# PSPS_AVNC_SRD_CS_combined-2021-02-07.net
KiCad netlist of a schematic drawn in EAGLE
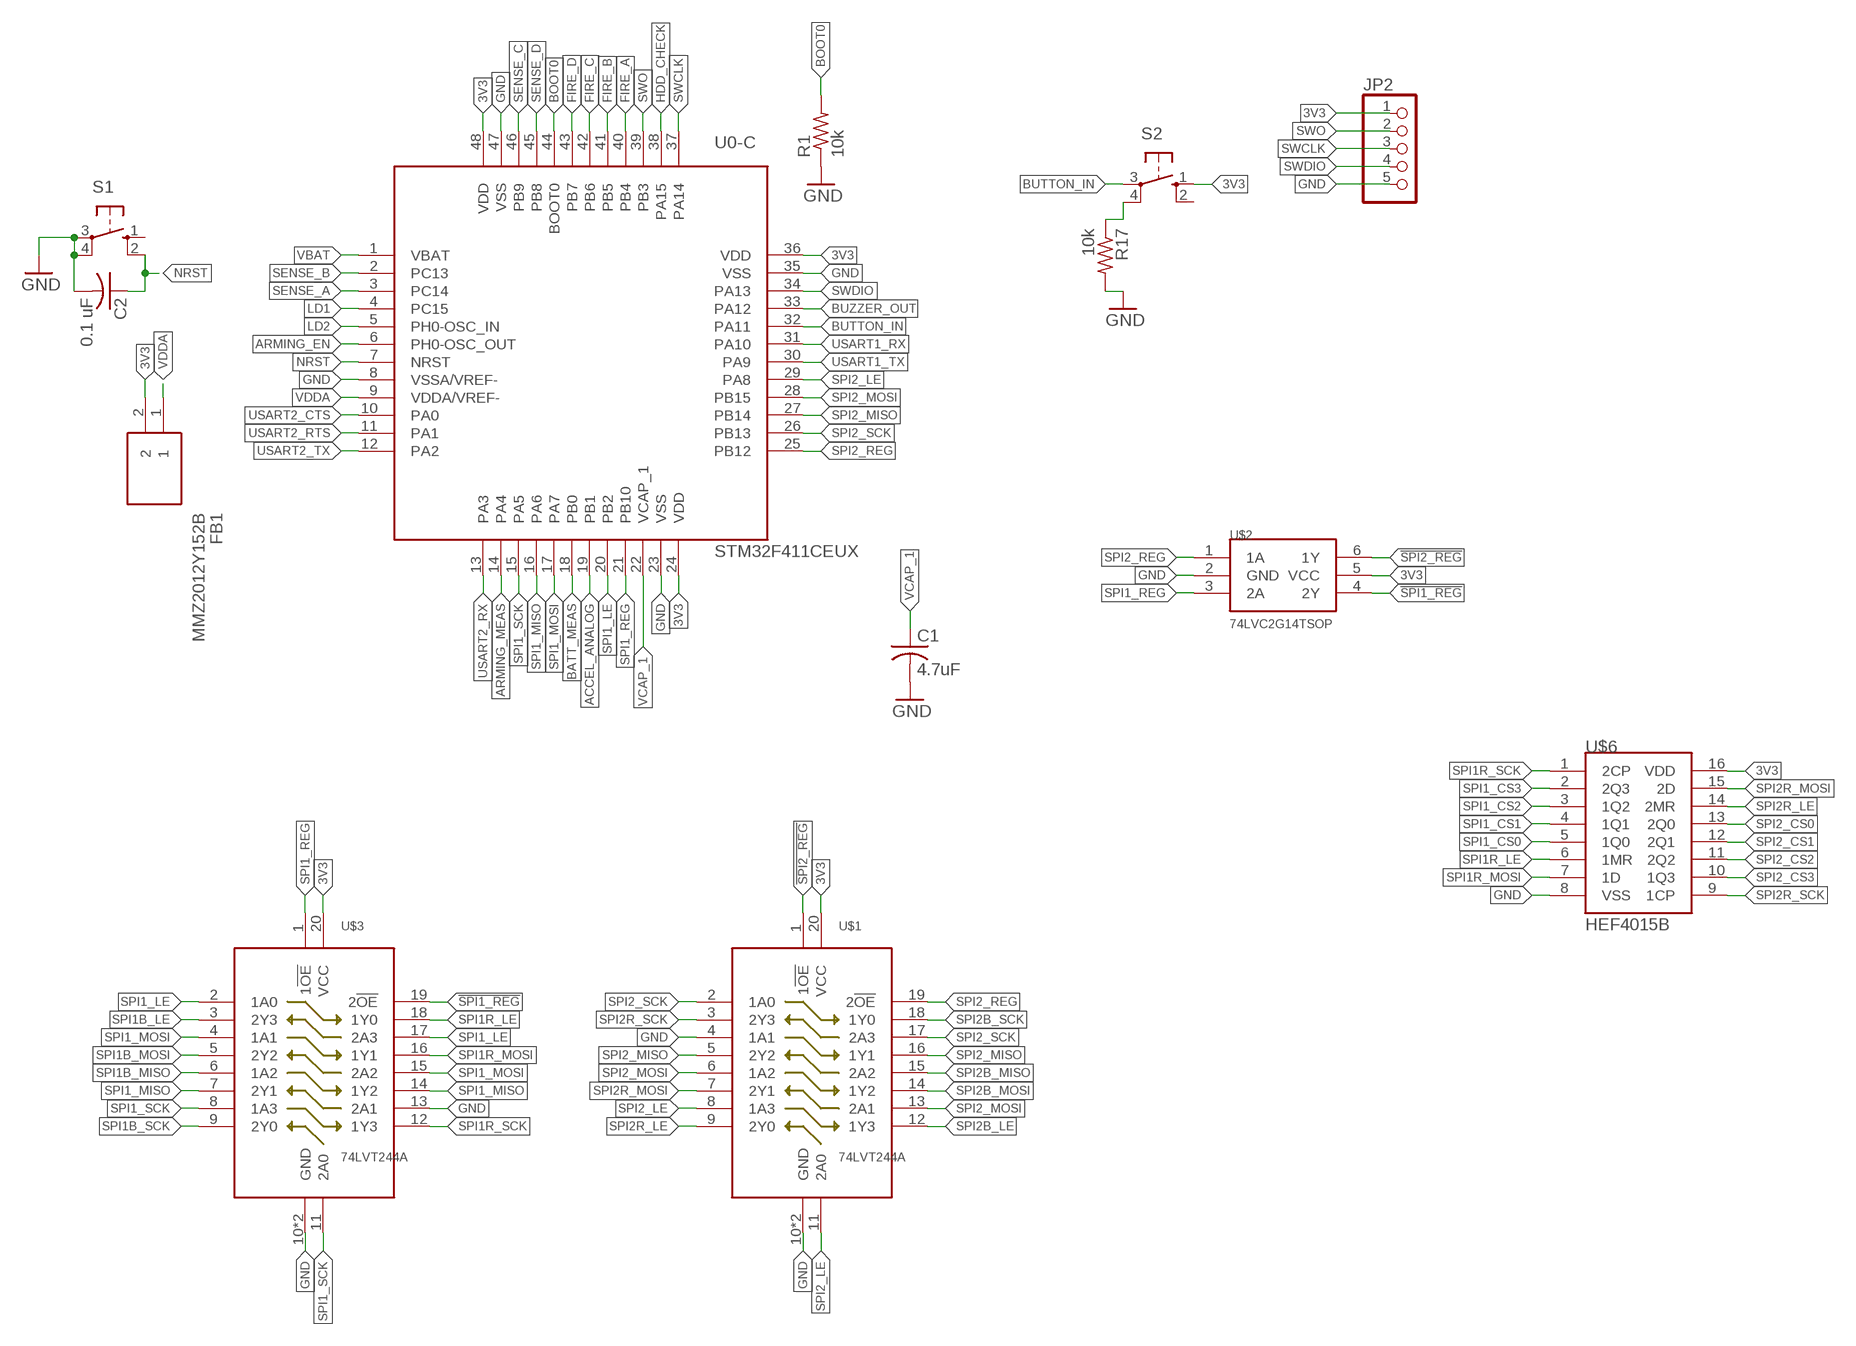
[diagram p0: schematic, sheet 1, part 1 of 2]
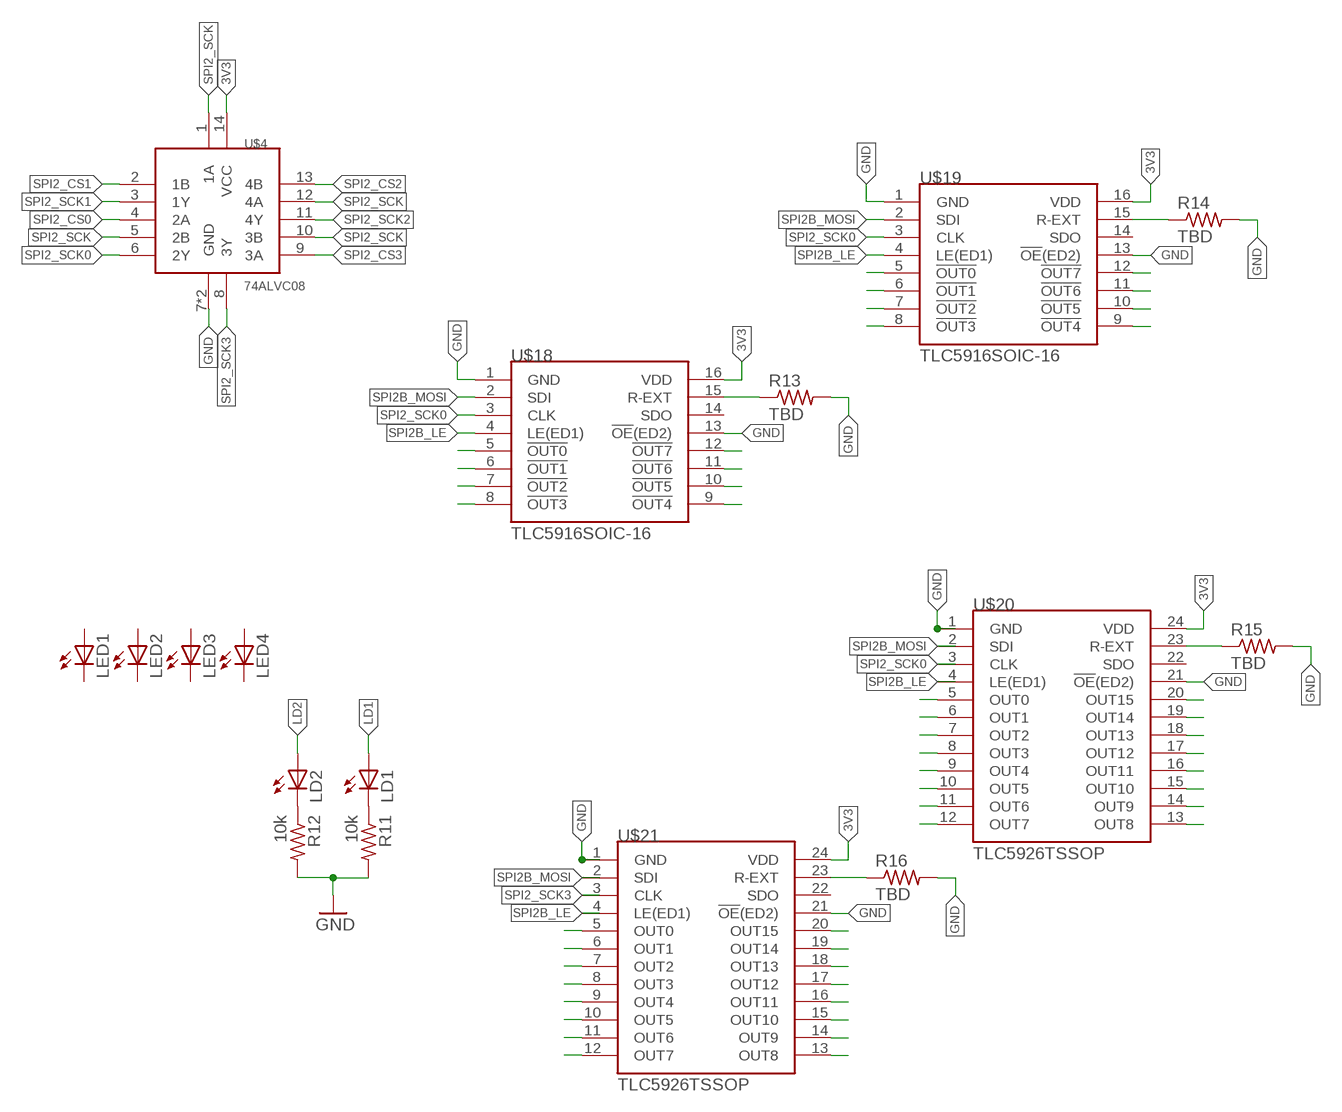
[diagram p1: schematic, sheet 1, part 2 of 2]
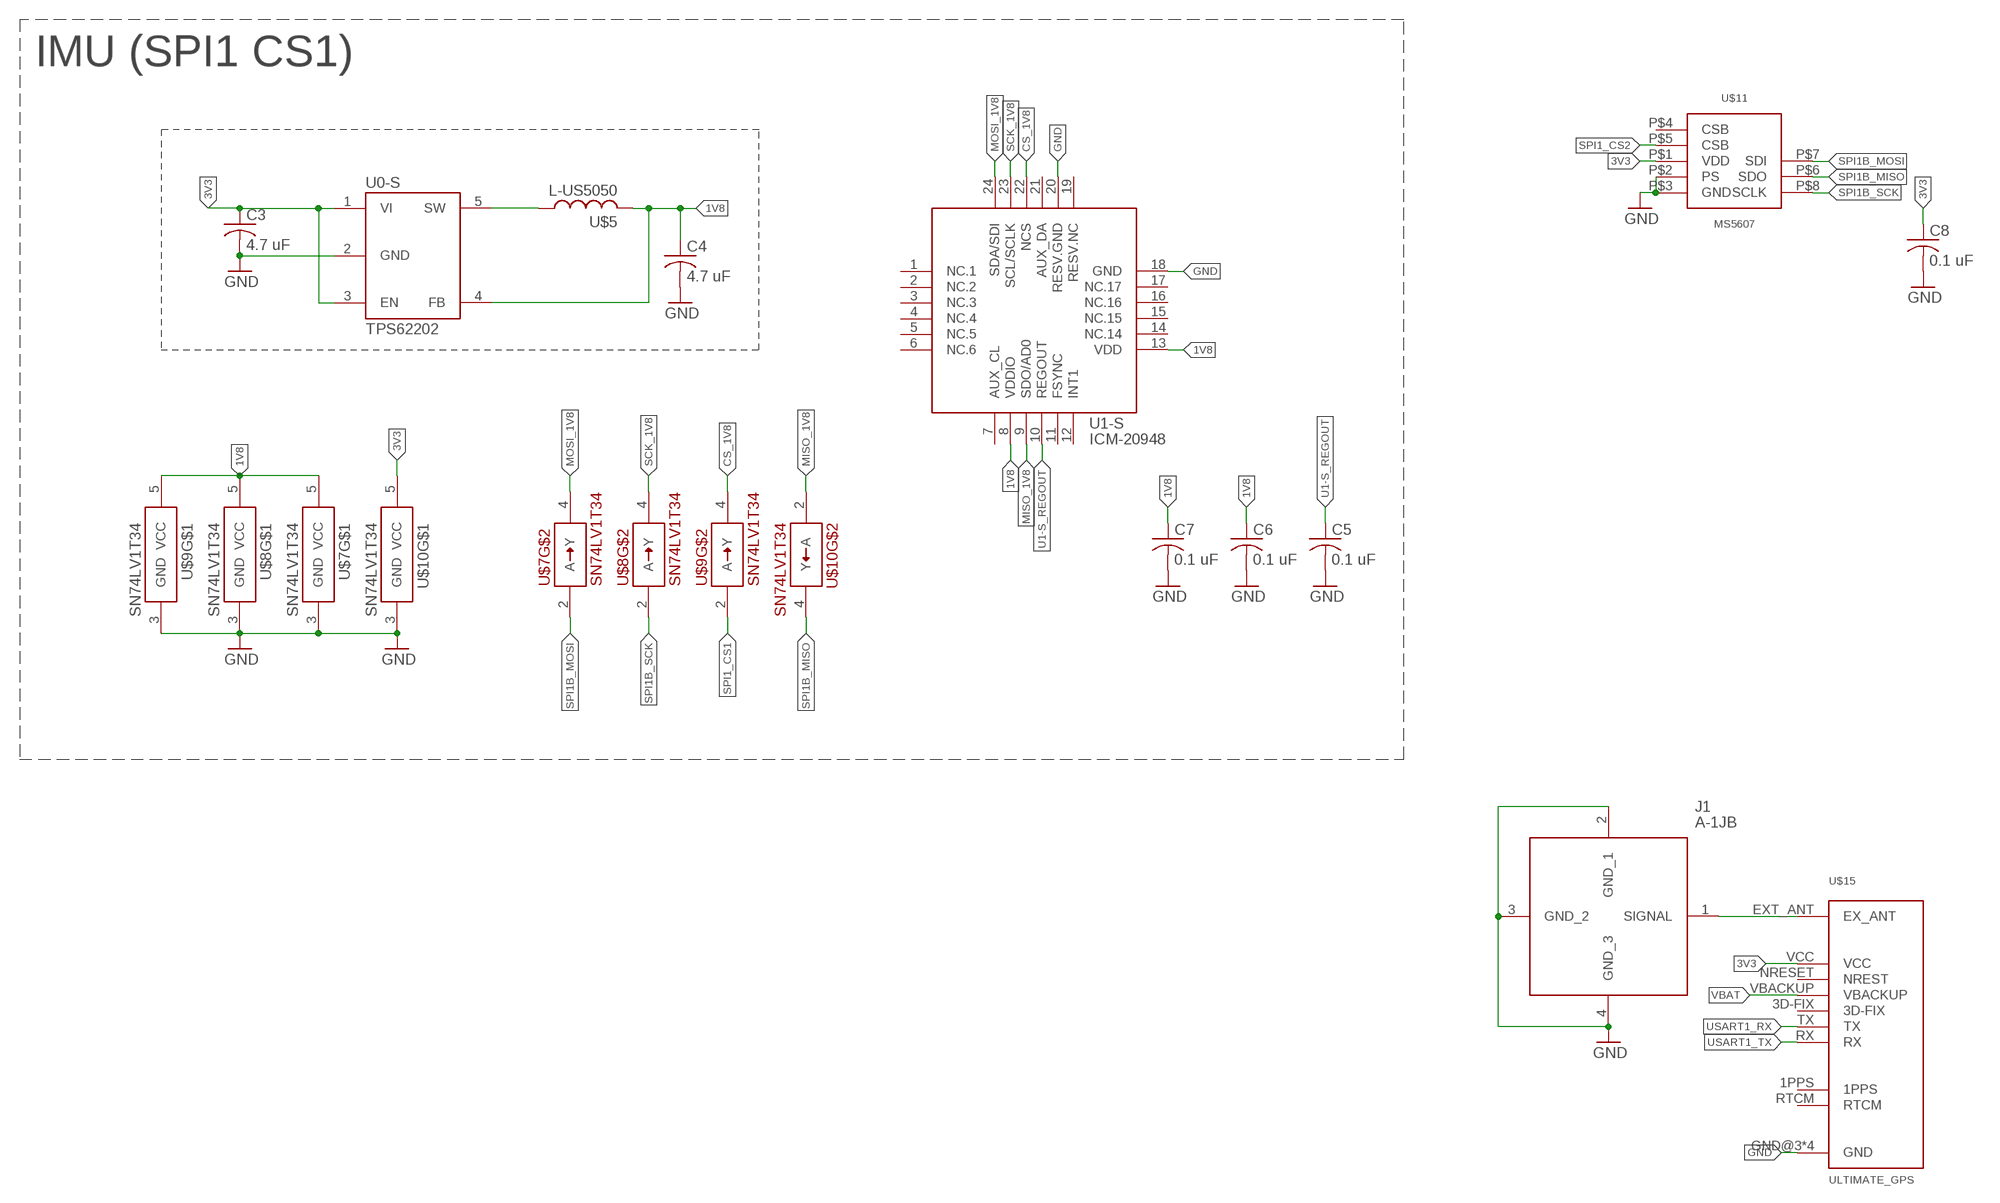
[diagram p2: schematic, sheet 2, part 1 of 2]
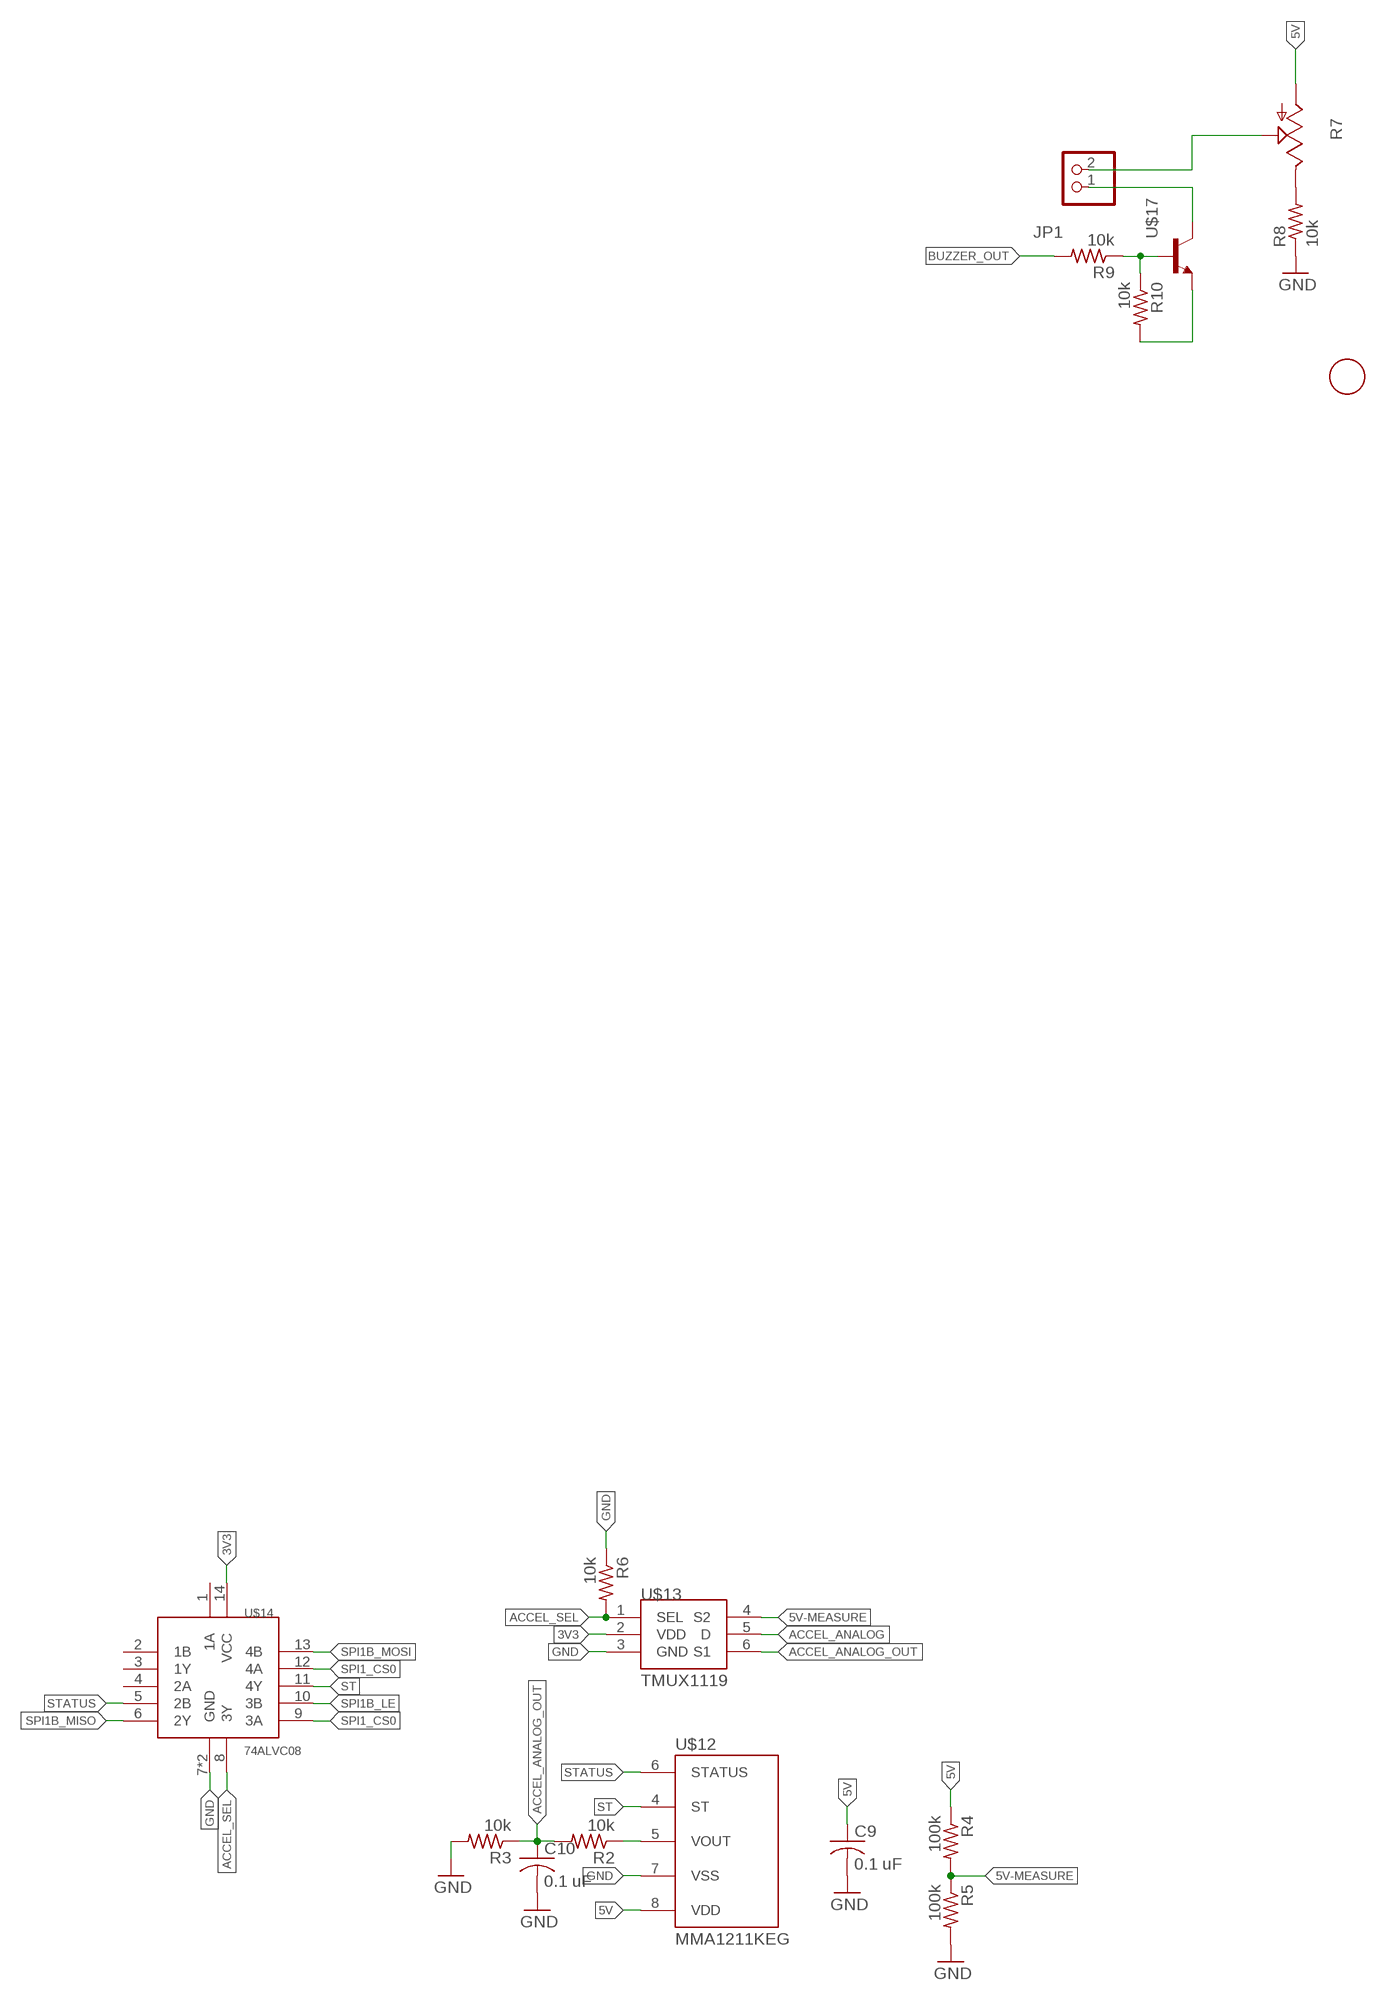
[diagram p3: schematic, sheet 2, part 2 of 2]

(export (version "E")
  (design (tool "Eeschema 10.0.6"))
  (components
    (comp (ref "C1")
      (value "4.7uF")
      (footprint "eagle-import:C0805")
      (libsource (lib "eagle-import") (part "C-USC0805"))
    )
    (comp (ref "C2")
      (value "0.1 uF")
      (footprint "eagle-import:C0805")
      (libsource (lib "eagle-import") (part "C-USC0805"))
    )
    (comp (ref "FB1")
      (value "MMZ2012Y152B")
      (footprint "eagle-import:BEADC2012X105N")
      (fields (field (name "MOUSER_PART_NUMBER") "810-MMZ2012Y152B"))
      (libsource (lib "eagle-import") (part "MMZ2012Y152B"))
    )
    (comp (ref "JP2")
      (value "PINHD-1X5")
      (footprint "eagle-import:1X05")
      (libsource (lib "eagle-import") (part "PINHD-1X5"))
    )
    (comp (ref "LD1")
      (value "LEDCHIP-LED0805")
      (footprint "eagle-import:CHIP-LED0805")
      (libsource (lib "eagle-import") (part "LEDCHIP-LED0805"))
    )
    (comp (ref "LD2")
      (value "LEDCHIP-LED0805")
      (footprint "eagle-import:CHIP-LED0805")
      (libsource (lib "eagle-import") (part "LEDCHIP-LED0805"))
    )
    (comp (ref "LED1")
      (value "LEDCHIP-LED0805")
      (footprint "eagle-import:CHIP-LED0805")
      (libsource (lib "eagle-import") (part "LEDCHIP-LED0805"))
    )
    (comp (ref "LED2")
      (value "LEDCHIP-LED0805")
      (footprint "eagle-import:CHIP-LED0805")
      (libsource (lib "eagle-import") (part "LEDCHIP-LED0805"))
    )
    (comp (ref "LED3")
      (value "LEDCHIP-LED0805")
      (footprint "eagle-import:CHIP-LED0805")
      (libsource (lib "eagle-import") (part "LEDCHIP-LED0805"))
    )
    (comp (ref "LED4")
      (value "LEDCHIP-LED0805")
      (footprint "eagle-import:CHIP-LED0805")
      (libsource (lib "eagle-import") (part "LEDCHIP-LED0805"))
    )
    (comp (ref "R1")
      (value "10k")
      (footprint "eagle-import:M0805")
      (libsource (lib "eagle-import") (part "R-US_M0805"))
    )
    (comp (ref "R11")
      (value "10k")
      (footprint "eagle-import:M0805")
      (libsource (lib "eagle-import") (part "R-US_M0805"))
    )
    (comp (ref "R12")
      (value "10k")
      (footprint "eagle-import:M0805")
      (libsource (lib "eagle-import") (part "R-US_M0805"))
    )
    (comp (ref "R13")
      (value "TBD")
      (footprint "eagle-import:M0805")
      (libsource (lib "eagle-import") (part "R-US_M0805"))
    )
    (comp (ref "R14")
      (value "TBD")
      (footprint "eagle-import:M0805")
      (libsource (lib "eagle-import") (part "R-US_M0805"))
    )
    (comp (ref "R15")
      (value "TBD")
      (footprint "eagle-import:M0805")
      (libsource (lib "eagle-import") (part "R-US_M0805"))
    )
    (comp (ref "R16")
      (value "TBD")
      (footprint "eagle-import:M0805")
      (libsource (lib "eagle-import") (part "R-US_M0805"))
    )
    (comp (ref "R17")
      (value "10k")
      (footprint "eagle-import:M0805")
      (libsource (lib "eagle-import") (part "R-US_M0805"))
    )
    (comp (ref "S1")
      (value "10-XX")
      (footprint "eagle-import:B3F-10XX")
      (fields (field (name "MPN") "B3F-1000"))
      (libsource (lib "eagle-import") (part "10-XX"))
    )
    (comp (ref "S2")
      (value "10-XX")
      (footprint "eagle-import:B3F-10XX")
      (fields (field (name "MPN") "B3F-1000"))
      (libsource (lib "eagle-import") (part "10-XX"))
    )
    (comp (ref "U$1")
      (value "74LVT244A")
      (footprint "eagle-import:QFN50P450X250X100-21T300X100N")
      (libsource (lib "eagle-import") (part "74LVT244A"))
    )
    (comp (ref "U$2")
      (value "74LVC2G14TSOP")
      (footprint "eagle-import:SOP95P280X110-6N")
      (libsource (lib "eagle-import") (part "74LVC2G14TSOP"))
    )
    (comp (ref "U$3")
      (value "74LVT244A")
      (footprint "eagle-import:QFN50P450X250X100-21T300X100N")
      (libsource (lib "eagle-import") (part "74LVT244A"))
    )
    (comp (ref "U$4")
      (value "74ALVC08")
      (footprint "eagle-import:QFN50P300X250X100-15T150X100N")
      (libsource (lib "eagle-import") (part "74ALVC08"))
    )
    (comp (ref "U$6")
      (value "HEF4015B")
      (footprint "eagle-import:SOIC127P600X265-16N")
      (libsource (lib "eagle-import") (part "HEF4015B"))
    )
    (comp (ref "U$18")
      (value "TLC5916SOIC-16")
      (footprint "eagle-import:SOIC127P600X175-16N")
      (libsource (lib "eagle-import") (part "TLC5916SOIC-16"))
    )
    (comp (ref "U$19")
      (value "TLC5916SOIC-16")
      (footprint "eagle-import:SOIC127P600X175-16N")
      (libsource (lib "eagle-import") (part "TLC5916SOIC-16"))
    )
    (comp (ref "U$20")
      (value "TLC5926TSSOP")
      (footprint "eagle-import:SOP65P640X120-24N")
      (libsource (lib "eagle-import") (part "TLC5926TSSOP"))
    )
    (comp (ref "U$21")
      (value "TLC5926TSSOP")
      (footprint "eagle-import:SOP65P640X120-24N")
      (libsource (lib "eagle-import") (part "TLC5926TSSOP"))
    )
    (comp (ref "U0-C")
      (value "STM32F411CEUX")
      (footprint "eagle-import:QFN50P700X700X50-49T560N")
      (libsource (lib "eagle-import") (part "STM32F411CEUX"))
    )
    (comp (ref "C3")
      (value "4.7 uF")
      (footprint "eagle-import:C0805")
      (libsource (lib "eagle-import") (part "C-USC0805"))
    )
    (comp (ref "C4")
      (value "4.7 uF")
      (footprint "eagle-import:C0805")
      (libsource (lib "eagle-import") (part "C-USC0805"))
    )
    (comp (ref "C5")
      (value "0.1 uF")
      (footprint "eagle-import:C0805")
      (libsource (lib "eagle-import") (part "C-USC0805"))
    )
    (comp (ref "C6")
      (value "0.1 uF")
      (footprint "eagle-import:C0805")
      (libsource (lib "eagle-import") (part "C-USC0805"))
    )
    (comp (ref "C7")
      (value "0.1 uF")
      (footprint "eagle-import:C0805")
      (libsource (lib "eagle-import") (part "C-USC0805"))
    )
    (comp (ref "C8")
      (value "0.1 uF")
      (footprint "eagle-import:C0805")
      (libsource (lib "eagle-import") (part "C-USC0805"))
    )
    (comp (ref "C9")
      (value "0.1 uF")
      (footprint "eagle-import:C0805")
      (libsource (lib "eagle-import") (part "C-USC0805"))
    )
    (comp (ref "C10")
      (value "0.1 uF")
      (footprint "eagle-import:C0805")
      (libsource (lib "eagle-import") (part "C-USC0805"))
    )
    (comp (ref "J1")
      (value "A-1JB")
      (footprint "eagle-import:A1JB")
      (fields (field (name "MOUSER_PART_NUMBER") "523-A-1JB"))
      (libsource (lib "eagle-import") (part "A-1JB"))
    )
    (comp (ref "JP1")
      (value "PINHD-1X2")
      (footprint "eagle-import:1X02")
      (libsource (lib "eagle-import") (part "PINHD-1X2"))
    )
    (comp (ref "R2")
      (value "10k")
      (footprint "eagle-import:M0805")
      (libsource (lib "eagle-import") (part "R-US_M0805"))
    )
    (comp (ref "R3")
      (value "10k")
      (footprint "eagle-import:M0805")
      (libsource (lib "eagle-import") (part "R-US_M0805"))
    )
    (comp (ref "R4")
      (value "100k")
      (footprint "eagle-import:M0805")
      (libsource (lib "eagle-import") (part "R-US_M0805"))
    )
    (comp (ref "R5")
      (value "100k")
      (footprint "eagle-import:M0805")
      (libsource (lib "eagle-import") (part "R-US_M0805"))
    )
    (comp (ref "R6")
      (value "10k")
      (footprint "eagle-import:M0805")
      (libsource (lib "eagle-import") (part "R-US_M0805"))
    )
    (comp (ref "R7")
      (value "TRIM_US-LI10")
      (footprint "eagle-import:LI10")
      (libsource (lib "eagle-import") (part "TRIM_US-LI10"))
    )
    (comp (ref "R8")
      (value "10k")
      (footprint "eagle-import:M0805")
      (libsource (lib "eagle-import") (part "R-US_M0805"))
    )
    (comp (ref "R9")
      (value "10k")
      (footprint "eagle-import:M0805")
      (libsource (lib "eagle-import") (part "R-US_M0805"))
    )
    (comp (ref "R10")
      (value "10k")
      (footprint "eagle-import:M0805")
      (libsource (lib "eagle-import") (part "R-US_M0805"))
    )
    (comp (ref "U$5")
      (value "L-US5050")
      (footprint "eagle-import:INDDFN1250X1250X600-2N")
      (libsource (lib "eagle-import") (part "L-US5050"))
    )
    (comp (ref "U$7")
      (value "SN74LV1T34")
      (footprint "eagle-import:SOT65P210X110-5")
      (libsource (lib "eagle-import") (part "SN74LV1T34"))
    )
    (comp (ref "U$8")
      (value "SN74LV1T34")
      (footprint "eagle-import:SOT65P210X110-5")
      (libsource (lib "eagle-import") (part "SN74LV1T34"))
    )
    (comp (ref "U$9")
      (value "SN74LV1T34")
      (footprint "eagle-import:SOT65P210X110-5")
      (libsource (lib "eagle-import") (part "SN74LV1T34"))
    )
    (comp (ref "U$10")
      (value "SN74LV1T34")
      (footprint "eagle-import:SOT65P210X110-5")
      (libsource (lib "eagle-import") (part "SN74LV1T34"))
    )
    (comp (ref "U$11")
      (value "MS5607")
      (footprint "eagle-import:MS5607")
      (libsource (lib "eagle-import") (part "MS5607"))
    )
    (comp (ref "U$12")
      (value "MMA1211KEG")
      (footprint "eagle-import:SOIC127P1041X355-16N")
      (libsource (lib "eagle-import") (part "MMA1211KEG"))
    )
    (comp (ref "U$13")
      (value "TMUX1119")
      (footprint "eagle-import:SOP95P280X145-6N")
      (libsource (lib "eagle-import") (part "TMUX1119"))
    )
    (comp (ref "U$14")
      (value "74ALVC08")
      (footprint "eagle-import:QFN50P300X250X100-15T150X100N")
      (libsource (lib "eagle-import") (part "74ALVC08"))
    )
    (comp (ref "U$15")
      (value "ULTIMATE_GPS")
      (footprint "eagle-import:FGPMMOPA6H")
      (libsource (lib "eagle-import") (part "ULTIMATE_GPS"))
    )
    (comp (ref "U$16")
      (value "UXCELL_BUZZER")
      (footprint "eagle-import:UXCELL_BUZZER")
      (libsource (lib "eagle-import") (part "UXCELL_BUZZER"))
    )
    (comp (ref "U$17")
      (value "NPN_TRANSISTOR")
      (footprint "eagle-import:SOT23")
      (libsource (lib "eagle-import") (part "NPN_TRANSISTOR"))
    )
    (comp (ref "U0-S")
      (value "TPS62202")
      (footprint "eagle-import:SOT95P280X145-5")
      (libsource (lib "eagle-import") (part "TPS62202"))
    )
    (comp (ref "U1-S")
      (value "ICM-20948")
      (footprint "eagle-import:QFN40P300X300X105-25T159X175")
      (libsource (lib "eagle-import") (part "ICM-20948"))
    )
  )
  (nets
    (net (code "1") (name "1V8") (class "Default")
      (node (ref "C4") (pin "1") (pinfunction "1_1") (pintype "passive"))
      (node (ref "C6") (pin "1") (pinfunction "1_1") (pintype "passive"))
      (node (ref "C7") (pin "1") (pinfunction "1_1") (pintype "passive"))
      (node (ref "U$5") (pin "2") (pinfunction "2_2") (pintype "passive"))
      (node (ref "U$7") (pin "5") (pinfunction "VCC_5") (pintype "bidirectional"))
      (node (ref "U$8") (pin "5") (pinfunction "VCC_5") (pintype "bidirectional"))
      (node (ref "U$9") (pin "5") (pinfunction "VCC_5") (pintype "bidirectional"))
      (node (ref "U0-S") (pin "4") (pinfunction "FB_4") (pintype "bidirectional"))
      (node (ref "U1-S") (pin "13") (pinfunction "VDD_13") (pintype "bidirectional"))
      (node (ref "U1-S") (pin "8") (pinfunction "VDDIO_8") (pintype "bidirectional"))
    )
    (net (code "2") (name "3V3") (class "Default")
      (node (ref "C3") (pin "1") (pinfunction "1_1") (pintype "passive"))
      (node (ref "C8") (pin "1") (pinfunction "1_1") (pintype "passive"))
      (node (ref "FB1") (pin "2") (pinfunction "2_2") (pintype "bidirectional"))
      (node (ref "JP2") (pin "1") (pinfunction "1_1") (pintype "passive"))
      (node (ref "S2") (pin "1") (pinfunction "S_1") (pintype "passive"))
      (node (ref "U$1") (pin "20") (pinfunction "VCC_20") (pintype "bidirectional"))
      (node (ref "U$10") (pin "5") (pinfunction "VCC_5") (pintype "bidirectional"))
      (node (ref "U$11") (pin "P$1") (pinfunction "VDD_P$1") (pintype "bidirectional"))
      (node (ref "U$13") (pin "2") (pinfunction "VDD_2") (pintype "bidirectional"))
      (node (ref "U$14") (pin "14") (pinfunction "VCC_14") (pintype "bidirectional"))
      (node (ref "U$15") (pin "VCC") (pinfunction "VCC_VCC") (pintype "bidirectional"))
      (node (ref "U$18") (pin "16") (pinfunction "VDD_16") (pintype "bidirectional"))
      (node (ref "U$19") (pin "16") (pinfunction "VDD_16") (pintype "bidirectional"))
      (node (ref "U$2") (pin "5") (pinfunction "VCC_5") (pintype "bidirectional"))
      (node (ref "U$20") (pin "24") (pinfunction "VDD_24") (pintype "bidirectional"))
      (node (ref "U$21") (pin "24") (pinfunction "VDD_24") (pintype "bidirectional"))
      (node (ref "U$3") (pin "20") (pinfunction "VCC_20") (pintype "bidirectional"))
      (node (ref "U$4") (pin "14") (pinfunction "VCC_14") (pintype "bidirectional"))
      (node (ref "U$6") (pin "16") (pinfunction "VDD_16") (pintype "bidirectional"))
      (node (ref "U0-C") (pin "24") (pinfunction "VDD_24") (pintype "bidirectional"))
      (node (ref "U0-C") (pin "36") (pinfunction "VDD_36") (pintype "bidirectional"))
      (node (ref "U0-C") (pin "48") (pinfunction "VDD_48") (pintype "bidirectional"))
      (node (ref "U0-S") (pin "1") (pinfunction "VI_1") (pintype "bidirectional"))
      (node (ref "U0-S") (pin "3") (pinfunction "EN_3") (pintype "bidirectional"))
    )
    (net (code "3") (name "5V") (class "Default")
      (node (ref "C9") (pin "1") (pinfunction "1_1") (pintype "passive"))
      (node (ref "R4") (pin "1") (pinfunction "1_1") (pintype "passive"))
      (node (ref "R7") (pin "A") (pinfunction "A_A") (pintype "passive"))
      (node (ref "U$12") (pin "8") (pinfunction "VDD_8") (pintype "bidirectional"))
    )
    (net (code "4") (name "5V-MEASURE") (class "Default")
      (node (ref "R4") (pin "2") (pinfunction "2_2") (pintype "passive"))
      (node (ref "R5") (pin "1") (pinfunction "1_1") (pintype "passive"))
      (node (ref "U$13") (pin "4") (pinfunction "S2_4") (pintype "bidirectional"))
    )
    (net (code "5") (name "ACCEL_ANALOG") (class "Default")
      (node (ref "U$13") (pin "5") (pinfunction "D_5") (pintype "bidirectional"))
      (node (ref "U0-C") (pin "19") (pinfunction "PB1_19") (pintype "bidirectional"))
    )
    (net (code "6") (name "ACCEL_ANALOG_OUT") (class "Default")
      (node (ref "C10") (pin "1") (pinfunction "1_1") (pintype "passive"))
      (node (ref "R2") (pin "2") (pinfunction "2_2") (pintype "passive"))
      (node (ref "R3") (pin "1") (pinfunction "1_1") (pintype "passive"))
      (node (ref "U$13") (pin "6") (pinfunction "S1_6") (pintype "bidirectional"))
    )
    (net (code "7") (name "ACCEL_SEL") (class "Default")
      (node (ref "R6") (pin "2") (pinfunction "2_2") (pintype "passive"))
      (node (ref "U$13") (pin "1") (pinfunction "SEL_1") (pintype "bidirectional"))
      (node (ref "U$14") (pin "8") (pinfunction "3Y_8") (pintype "bidirectional"))
    )
    (net (code "8") (name "ARMING_EN") (class "Default")
      (node (ref "U0-C") (pin "6") (pinfunction "PH0-OSC_OUT_6") (pintype "bidirectional"))
    )
    (net (code "9") (name "ARMING_MEAS") (class "Default")
      (node (ref "U0-C") (pin "14") (pinfunction "PA4_14") (pintype "bidirectional"))
    )
    (net (code "10") (name "BATT_MEAS") (class "Default")
      (node (ref "U0-C") (pin "18") (pinfunction "PB0_18") (pintype "bidirectional"))
    )
    (net (code "11") (name "BOOT0") (class "Default")
      (node (ref "R1") (pin "2") (pinfunction "2_2") (pintype "passive"))
      (node (ref "U0-C") (pin "44") (pinfunction "BOOT0_44") (pintype "bidirectional"))
    )
    (net (code "12") (name "BUTTON_IN") (class "Default")
      (node (ref "S2") (pin "3") (pinfunction "P_3") (pintype "passive"))
      (node (ref "U0-C") (pin "32") (pinfunction "PA11_32") (pintype "bidirectional"))
    )
    (net (code "13") (name "BUZZER_OUT") (class "Default")
      (node (ref "R9") (pin "2") (pinfunction "2_2") (pintype "passive"))
      (node (ref "U0-C") (pin "33") (pinfunction "PA12_33") (pintype "bidirectional"))
    )
    (net (code "14") (name "CS_1V8") (class "Default")
      (node (ref "U$9") (pin "4") (pinfunction "Y_4") (pintype "bidirectional"))
      (node (ref "U1-S") (pin "22") (pinfunction "NCS_22") (pintype "bidirectional"))
    )
    (net (code "15") (name "FIRE_A") (class "Default")
      (node (ref "U0-C") (pin "40") (pinfunction "PB4_40") (pintype "bidirectional"))
    )
    (net (code "16") (name "FIRE_B") (class "Default")
      (node (ref "U0-C") (pin "41") (pinfunction "PB5_41") (pintype "bidirectional"))
    )
    (net (code "17") (name "FIRE_C") (class "Default")
      (node (ref "U0-C") (pin "42") (pinfunction "PB6_42") (pintype "bidirectional"))
    )
    (net (code "18") (name "FIRE_D") (class "Default")
      (node (ref "U0-C") (pin "43") (pinfunction "PB7_43") (pintype "bidirectional"))
    )
    (net (code "19") (name "GND") (class "Default")
      (node (ref "C1") (pin "2") (pinfunction "2_2") (pintype "passive"))
      (node (ref "C10") (pin "2") (pinfunction "2_2") (pintype "passive"))
      (node (ref "C2") (pin "2") (pinfunction "2_2") (pintype "passive"))
      (node (ref "C3") (pin "2") (pinfunction "2_2") (pintype "passive"))
      (node (ref "C4") (pin "2") (pinfunction "2_2") (pintype "passive"))
      (node (ref "C5") (pin "2") (pinfunction "2_2") (pintype "passive"))
      (node (ref "C6") (pin "2") (pinfunction "2_2") (pintype "passive"))
      (node (ref "C7") (pin "2") (pinfunction "2_2") (pintype "passive"))
      (node (ref "C8") (pin "2") (pinfunction "2_2") (pintype "passive"))
      (node (ref "C9") (pin "2") (pinfunction "2_2") (pintype "passive"))
      (node (ref "J1") (pin "2") (pinfunction "GND_1_2") (pintype "bidirectional"))
      (node (ref "J1") (pin "3") (pinfunction "GND_2_3") (pintype "bidirectional"))
      (node (ref "J1") (pin "4") (pinfunction "GND_3_4") (pintype "bidirectional"))
      (node (ref "JP2") (pin "5") (pinfunction "5_5") (pintype "passive"))
      (node (ref "R1") (pin "1") (pinfunction "1_1") (pintype "passive"))
      (node (ref "R11") (pin "2") (pinfunction "2_2") (pintype "passive"))
      (node (ref "R12") (pin "2") (pinfunction "2_2") (pintype "passive"))
      (node (ref "R13") (pin "2") (pinfunction "2_2") (pintype "passive"))
      (node (ref "R14") (pin "2") (pinfunction "2_2") (pintype "passive"))
      (node (ref "R15") (pin "2") (pinfunction "2_2") (pintype "passive"))
      (node (ref "R16") (pin "2") (pinfunction "2_2") (pintype "passive"))
      (node (ref "R17") (pin "2") (pinfunction "2_2") (pintype "passive"))
      (node (ref "R3") (pin "2") (pinfunction "2_2") (pintype "passive"))
      (node (ref "R5") (pin "2") (pinfunction "2_2") (pintype "passive"))
      (node (ref "R6") (pin "1") (pinfunction "1_1") (pintype "passive"))
      (node (ref "R8") (pin "1") (pinfunction "1_1") (pintype "passive"))
      (node (ref "S1") (pin "3") (pinfunction "P_3") (pintype "passive"))
      (node (ref "S1") (pin "4") (pinfunction "P1_4") (pintype "passive"))
      (node (ref "U$1") (pin "10") (pinfunction "GND_10") (pintype "bidirectional"))
      (node (ref "U$1") (pin "21") (pinfunction "GND_21") (pintype "bidirectional"))
      (node (ref "U$1") (pin "4") (pinfunction "1A1_4") (pintype "bidirectional"))
      (node (ref "U$10") (pin "3") (pinfunction "GND_3") (pintype "bidirectional"))
      (node (ref "U$11") (pin "P$2") (pinfunction "PS_P$2") (pintype "bidirectional"))
      (node (ref "U$11") (pin "P$3") (pinfunction "GND_P$3") (pintype "bidirectional"))
      (node (ref "U$12") (pin "7") (pinfunction "VSS_7") (pintype "bidirectional"))
      (node (ref "U$13") (pin "3") (pinfunction "GND_3") (pintype "bidirectional"))
      (node (ref "U$14") (pin "15") (pinfunction "GND_15") (pintype "bidirectional"))
      (node (ref "U$14") (pin "7") (pinfunction "GND_7") (pintype "bidirectional"))
      (node (ref "U$15") (pin "GND@12") (pinfunction "GND_GND@12") (pintype "bidirectional"))
      (node (ref "U$15") (pin "GND@19") (pinfunction "GND_GND@19") (pintype "bidirectional"))
      (node (ref "U$15") (pin "GND@3") (pinfunction "GND_GND@3") (pintype "bidirectional"))
      (node (ref "U$15") (pin "GND@8") (pinfunction "GND_GND@8") (pintype "bidirectional"))
      (node (ref "U$18") (pin "1") (pinfunction "GND_1") (pintype "bidirectional"))
      (node (ref "U$18") (pin "13") (pinfunction "~{OE}(ED2)_13") (pintype "bidirectional"))
      (node (ref "U$19") (pin "1") (pinfunction "GND_1") (pintype "bidirectional"))
      (node (ref "U$19") (pin "13") (pinfunction "~{OE}(ED2)_13") (pintype "bidirectional"))
      (node (ref "U$2") (pin "2") (pinfunction "GND_2") (pintype "bidirectional"))
      (node (ref "U$20") (pin "1") (pinfunction "GND_1") (pintype "bidirectional"))
      (node (ref "U$20") (pin "21") (pinfunction "~{OE}(ED2)_21") (pintype "bidirectional"))
      (node (ref "U$21") (pin "1") (pinfunction "GND_1") (pintype "bidirectional"))
      (node (ref "U$21") (pin "21") (pinfunction "~{OE}(ED2)_21") (pintype "bidirectional"))
      (node (ref "U$3") (pin "10") (pinfunction "GND_10") (pintype "bidirectional"))
      (node (ref "U$3") (pin "13") (pinfunction "2A1_13") (pintype "bidirectional"))
      (node (ref "U$3") (pin "21") (pinfunction "GND_21") (pintype "bidirectional"))
      (node (ref "U$4") (pin "15") (pinfunction "GND_15") (pintype "bidirectional"))
      (node (ref "U$4") (pin "7") (pinfunction "GND_7") (pintype "bidirectional"))
      (node (ref "U$6") (pin "8") (pinfunction "VSS_8") (pintype "bidirectional"))
      (node (ref "U$7") (pin "3") (pinfunction "GND_3") (pintype "bidirectional"))
      (node (ref "U$8") (pin "3") (pinfunction "GND_3") (pintype "bidirectional"))
      (node (ref "U$9") (pin "3") (pinfunction "GND_3") (pintype "bidirectional"))
      (node (ref "U0-C") (pin "23") (pinfunction "VSS_23") (pintype "bidirectional"))
      (node (ref "U0-C") (pin "35") (pinfunction "VSS_35") (pintype "bidirectional"))
      (node (ref "U0-C") (pin "47") (pinfunction "VSS_47") (pintype "bidirectional"))
      (node (ref "U0-C") (pin "8") (pinfunction "VSSA/VREF-_8") (pintype "bidirectional"))
      (node (ref "U0-S") (pin "2") (pinfunction "GND_2") (pintype "bidirectional"))
      (node (ref "U1-S") (pin "18") (pinfunction "GND_18") (pintype "bidirectional"))
      (node (ref "U1-S") (pin "20") (pinfunction "RESV.GND_20") (pintype "bidirectional"))
    )
    (net (code "20") (name "HDD_CHECK") (class "Default")
      (node (ref "U0-C") (pin "38") (pinfunction "PA15_38") (pintype "bidirectional"))
    )
    (net (code "21") (name "LD1") (class "Default")
      (node (ref "LD1") (pin "A") (pinfunction "A_A") (pintype "passive"))
      (node (ref "U0-C") (pin "4") (pinfunction "PC15_4") (pintype "bidirectional"))
    )
    (net (code "22") (name "LD2") (class "Default")
      (node (ref "LD2") (pin "A") (pinfunction "A_A") (pintype "passive"))
      (node (ref "U0-C") (pin "5") (pinfunction "PH0-OSC_IN_5") (pintype "bidirectional"))
    )
    (net (code "23") (name "MISO_1V8") (class "Default")
      (node (ref "U$10") (pin "2") (pinfunction "A_2") (pintype "bidirectional"))
      (node (ref "U1-S") (pin "9") (pinfunction "SDO/AD0_9") (pintype "bidirectional"))
    )
    (net (code "24") (name "MOSI_1V8") (class "Default")
      (node (ref "U$7") (pin "4") (pinfunction "Y_4") (pintype "bidirectional"))
      (node (ref "U1-S") (pin "24") (pinfunction "SDA/SDI_24") (pintype "bidirectional"))
    )
    (net (code "25") (name "NRST") (class "Default")
      (node (ref "C2") (pin "1") (pinfunction "1_1") (pintype "passive"))
      (node (ref "S1") (pin "2") (pinfunction "S1_2") (pintype "passive"))
      (node (ref "U0-C") (pin "7") (pinfunction "NRST_7") (pintype "bidirectional"))
    )
    (net (code "26") (name "Net-(J1-SIGNAL)") (class "Default")
      (node (ref "J1") (pin "1") (pinfunction "SIGNAL_1") (pintype "bidirectional"))
      (node (ref "U$15") (pin "EXT_ANT") (pinfunction "EX_ANT_EXT_ANT") (pintype "bidirectional"))
    )
    (net (code "27") (name "Net-(JP1-Pad2)") (class "Default")
      (node (ref "JP1") (pin "2") (pinfunction "2_2") (pintype "passive"))
      (node (ref "R7") (pin "S") (pinfunction "S_S") (pintype "passive"))
    )
    (net (code "28") (name "Net-(LD1-PadC)") (class "Default")
      (node (ref "LD1") (pin "C") (pinfunction "C_C") (pintype "passive"))
      (node (ref "R11") (pin "1") (pinfunction "1_1") (pintype "passive"))
    )
    (net (code "29") (name "Net-(LD2-PadC)") (class "Default")
      (node (ref "LD2") (pin "C") (pinfunction "C_C") (pintype "passive"))
      (node (ref "R12") (pin "1") (pinfunction "1_1") (pintype "passive"))
    )
    (net (code "30") (name "Net-(R7-PadE)") (class "Default")
      (node (ref "R7") (pin "E") (pinfunction "E_E") (pintype "passive"))
      (node (ref "R8") (pin "2") (pinfunction "2_2") (pintype "passive"))
    )
    (net (code "31") (name "Net-(S2-P1)") (class "Default")
      (node (ref "R17") (pin "1") (pinfunction "1_1") (pintype "passive"))
      (node (ref "S2") (pin "4") (pinfunction "P1_4") (pintype "passive"))
    )
    (net (code "32") (name "Net-(U$12-VOUT)") (class "Default")
      (node (ref "R2") (pin "1") (pinfunction "1_1") (pintype "passive"))
      (node (ref "U$12") (pin "5") (pinfunction "VOUT_5") (pintype "bidirectional"))
    )
    (net (code "33") (name "Net-(U$17-B)") (class "Default")
      (node (ref "R10") (pin "1") (pinfunction "1_1") (pintype "passive"))
      (node (ref "R9") (pin "1") (pinfunction "1_1") (pintype "passive"))
      (node (ref "U$17") (pin "1") (pinfunction "B_1") (pintype "passive"))
    )
    (net (code "34") (name "Net-(U$17-C)") (class "Default")
      (node (ref "JP1") (pin "1") (pinfunction "1_1") (pintype "passive"))
      (node (ref "U$17") (pin "2") (pinfunction "C_2") (pintype "passive"))
    )
    (net (code "35") (name "Net-(U$17-E)") (class "Default")
      (node (ref "R10") (pin "2") (pinfunction "2_2") (pintype "passive"))
      (node (ref "U$17") (pin "3") (pinfunction "E_3") (pintype "passive"))
    )
    (net (code "36") (name "Net-(U$18-R-EXT)") (class "Default")
      (node (ref "R13") (pin "1") (pinfunction "1_1") (pintype "passive"))
      (node (ref "U$18") (pin "15") (pinfunction "R-EXT_15") (pintype "bidirectional"))
    )
    (net (code "37") (name "Net-(U$19-R-EXT)") (class "Default")
      (node (ref "R14") (pin "1") (pinfunction "1_1") (pintype "passive"))
      (node (ref "U$19") (pin "15") (pinfunction "R-EXT_15") (pintype "bidirectional"))
    )
    (net (code "38") (name "Net-(U$20-R-EXT)") (class "Default")
      (node (ref "R15") (pin "1") (pinfunction "1_1") (pintype "passive"))
      (node (ref "U$20") (pin "23") (pinfunction "R-EXT_23") (pintype "bidirectional"))
    )
    (net (code "39") (name "Net-(U$21-R-EXT)") (class "Default")
      (node (ref "R16") (pin "1") (pinfunction "1_1") (pintype "passive"))
      (node (ref "U$21") (pin "23") (pinfunction "R-EXT_23") (pintype "bidirectional"))
    )
    (net (code "40") (name "Net-(U0-S-SW)") (class "Default")
      (node (ref "U$5") (pin "1") (pinfunction "1_1") (pintype "passive"))
      (node (ref "U0-S") (pin "5") (pinfunction "SW_5") (pintype "bidirectional"))
    )
    (net (code "41") (name "SCK_1V8") (class "Default")
      (node (ref "U$8") (pin "4") (pinfunction "Y_4") (pintype "bidirectional"))
      (node (ref "U1-S") (pin "23") (pinfunction "SCL/SCLK_23") (pintype "bidirectional"))
    )
    (net (code "42") (name "SENSE_A") (class "Default")
      (node (ref "U0-C") (pin "3") (pinfunction "PC14_3") (pintype "bidirectional"))
    )
    (net (code "43") (name "SENSE_B") (class "Default")
      (node (ref "U0-C") (pin "2") (pinfunction "PC13_2") (pintype "bidirectional"))
    )
    (net (code "44") (name "SENSE_C") (class "Default")
      (node (ref "U0-C") (pin "46") (pinfunction "PB9_46") (pintype "bidirectional"))
    )
    (net (code "45") (name "SENSE_D") (class "Default")
      (node (ref "U0-C") (pin "45") (pinfunction "PB8_45") (pintype "bidirectional"))
    )
    (net (code "46") (name "SPI1B_LE") (class "Default")
      (node (ref "U$14") (pin "10") (pinfunction "3B_10") (pintype "bidirectional"))
      (node (ref "U$3") (pin "3") (pinfunction "2Y3_3") (pintype "bidirectional"))
    )
    (net (code "47") (name "SPI1B_MISO") (class "Default")
      (node (ref "U$10") (pin "4") (pinfunction "Y_4") (pintype "bidirectional"))
      (node (ref "U$11") (pin "P$6") (pinfunction "SDO_P$6") (pintype "bidirectional"))
      (node (ref "U$14") (pin "6") (pinfunction "2Y_6") (pintype "bidirectional"))
      (node (ref "U$3") (pin "6") (pinfunction "1A2_6") (pintype "bidirectional"))
    )
    (net (code "48") (name "SPI1B_MOSI") (class "Default")
      (node (ref "U$11") (pin "P$7") (pinfunction "SDI_P$7") (pintype "bidirectional"))
      (node (ref "U$14") (pin "13") (pinfunction "4B_13") (pintype "bidirectional"))
      (node (ref "U$3") (pin "5") (pinfunction "2Y2_5") (pintype "bidirectional"))
      (node (ref "U$7") (pin "2") (pinfunction "A_2") (pintype "bidirectional"))
    )
    (net (code "49") (name "SPI1B_SCK") (class "Default")
      (node (ref "U$11") (pin "P$8") (pinfunction "SCLK_P$8") (pintype "bidirectional"))
      (node (ref "U$3") (pin "9") (pinfunction "2Y0_9") (pintype "bidirectional"))
      (node (ref "U$8") (pin "2") (pinfunction "A_2") (pintype "bidirectional"))
    )
    (net (code "50") (name "SPI1R_LE") (class "Default")
      (node (ref "U$3") (pin "18") (pinfunction "1Y0_18") (pintype "bidirectional"))
      (node (ref "U$6") (pin "6") (pinfunction "1MR_6") (pintype "bidirectional"))
    )
    (net (code "51") (name "SPI1R_MOSI") (class "Default")
      (node (ref "U$3") (pin "16") (pinfunction "1Y1_16") (pintype "bidirectional"))
      (node (ref "U$6") (pin "7") (pinfunction "1D_7") (pintype "bidirectional"))
    )
    (net (code "52") (name "SPI1R_SCK") (class "Default")
      (node (ref "U$3") (pin "12") (pinfunction "1Y3_12") (pintype "bidirectional"))
      (node (ref "U$6") (pin "1") (pinfunction "2CP_1") (pintype "bidirectional"))
    )
    (net (code "53") (name "SPI1_CS0") (class "Default")
      (node (ref "U$14") (pin "12") (pinfunction "4A_12") (pintype "bidirectional"))
      (node (ref "U$14") (pin "9") (pinfunction "3A_9") (pintype "bidirectional"))
      (node (ref "U$6") (pin "5") (pinfunction "1Q0_5") (pintype "bidirectional"))
    )
    (net (code "54") (name "SPI1_CS1") (class "Default")
      (node (ref "U$6") (pin "4") (pinfunction "1Q1_4") (pintype "bidirectional"))
      (node (ref "U$9") (pin "2") (pinfunction "A_2") (pintype "bidirectional"))
    )
    (net (code "55") (name "SPI1_CS2") (class "Default")
      (node (ref "U$11") (pin "P$5") (pinfunction "CSB_P$5") (pintype "bidirectional"))
      (node (ref "U$6") (pin "3") (pinfunction "1Q2_3") (pintype "bidirectional"))
    )
    (net (code "56") (name "SPI1_CS3") (class "Default")
      (node (ref "U$6") (pin "2") (pinfunction "2Q3_2") (pintype "bidirectional"))
    )
    (net (code "57") (name "SPI1_LE") (class "Default")
      (node (ref "U$3") (pin "17") (pinfunction "2A3_17") (pintype "bidirectional"))
      (node (ref "U$3") (pin "2") (pinfunction "1A0_2") (pintype "bidirectional"))
      (node (ref "U0-C") (pin "20") (pinfunction "PB2_20") (pintype "bidirectional"))
    )
    (net (code "58") (name "SPI1_MISO") (class "Default")
      (node (ref "U$3") (pin "14") (pinfunction "1Y2_14") (pintype "bidirectional"))
      (node (ref "U$3") (pin "7") (pinfunction "2Y1_7") (pintype "bidirectional"))
      (node (ref "U0-C") (pin "16") (pinfunction "PA6_16") (pintype "bidirectional"))
    )
    (net (code "59") (name "SPI1_MOSI") (class "Default")
      (node (ref "U$3") (pin "15") (pinfunction "2A2_15") (pintype "bidirectional"))
      (node (ref "U$3") (pin "4") (pinfunction "1A1_4") (pintype "bidirectional"))
      (node (ref "U0-C") (pin "17") (pinfunction "PA7_17") (pintype "bidirectional"))
    )
    (net (code "60") (name "SPI1_REG") (class "Default")
      (node (ref "U$2") (pin "3") (pinfunction "2A_3") (pintype "bidirectional"))
      (node (ref "U$3") (pin "1") (pinfunction "1~{OE}_1") (pintype "bidirectional"))
      (node (ref "U0-C") (pin "21") (pinfunction "PB10_21") (pintype "bidirectional"))
    )
    (net (code "61") (name "SPI1_SCK") (class "Default")
      (node (ref "U$3") (pin "11") (pinfunction "2A0_11") (pintype "bidirectional"))
      (node (ref "U$3") (pin "8") (pinfunction "1A3_8") (pintype "bidirectional"))
      (node (ref "U0-C") (pin "15") (pinfunction "PA5_15") (pintype "bidirectional"))
    )
    (net (code "62") (name "SPI2B_LE") (class "Default")
      (node (ref "U$1") (pin "12") (pinfunction "1Y3_12") (pintype "bidirectional"))
      (node (ref "U$18") (pin "4") (pinfunction "LE(ED1)_4") (pintype "bidirectional"))
      (node (ref "U$19") (pin "4") (pinfunction "LE(ED1)_4") (pintype "bidirectional"))
      (node (ref "U$20") (pin "4") (pinfunction "LE(ED1)_4") (pintype "bidirectional"))
      (node (ref "U$21") (pin "4") (pinfunction "LE(ED1)_4") (pintype "bidirectional"))
    )
    (net (code "63") (name "SPI2B_MISO") (class "Default")
      (node (ref "U$1") (pin "15") (pinfunction "2A2_15") (pintype "bidirectional"))
    )
    (net (code "64") (name "SPI2B_MOSI") (class "Default")
      (node (ref "U$1") (pin "14") (pinfunction "1Y2_14") (pintype "bidirectional"))
      (node (ref "U$18") (pin "2") (pinfunction "SDI_2") (pintype "bidirectional"))
      (node (ref "U$19") (pin "2") (pinfunction "SDI_2") (pintype "bidirectional"))
      (node (ref "U$20") (pin "2") (pinfunction "SDI_2") (pintype "bidirectional"))
      (node (ref "U$21") (pin "2") (pinfunction "SDI_2") (pintype "bidirectional"))
    )
    (net (code "65") (name "SPI2B_SCK") (class "Default")
      (node (ref "U$1") (pin "18") (pinfunction "1Y0_18") (pintype "bidirectional"))
    )
    (net (code "66") (name "SPI2R_LE") (class "Default")
      (node (ref "U$1") (pin "9") (pinfunction "2Y0_9") (pintype "bidirectional"))
      (node (ref "U$6") (pin "14") (pinfunction "2MR_14") (pintype "bidirectional"))
    )
    (net (code "67") (name "SPI2R_MOSI") (class "Default")
      (node (ref "U$1") (pin "7") (pinfunction "2Y1_7") (pintype "bidirectional"))
      (node (ref "U$6") (pin "15") (pinfunction "2D_15") (pintype "bidirectional"))
    )
    (net (code "68") (name "SPI2R_SCK") (class "Default")
      (node (ref "U$1") (pin "3") (pinfunction "2Y3_3") (pintype "bidirectional"))
      (node (ref "U$6") (pin "9") (pinfunction "1CP_9") (pintype "bidirectional"))
    )
    (net (code "69") (name "SPI2_CS0") (class "Default")
      (node (ref "U$4") (pin "4") (pinfunction "2A_4") (pintype "bidirectional"))
      (node (ref "U$6") (pin "13") (pinfunction "2Q0_13") (pintype "bidirectional"))
    )
    (net (code "70") (name "SPI2_CS1") (class "Default")
      (node (ref "U$4") (pin "2") (pinfunction "1B_2") (pintype "bidirectional"))
      (node (ref "U$6") (pin "12") (pinfunction "2Q1_12") (pintype "bidirectional"))
    )
    (net (code "71") (name "SPI2_CS2") (class "Default")
      (node (ref "U$4") (pin "13") (pinfunction "4B_13") (pintype "bidirectional"))
      (node (ref "U$6") (pin "11") (pinfunction "2Q2_11") (pintype "bidirectional"))
    )
    (net (code "72") (name "SPI2_CS3") (class "Default")
      (node (ref "U$4") (pin "9") (pinfunction "3A_9") (pintype "bidirectional"))
      (node (ref "U$6") (pin "10") (pinfunction "1Q3_10") (pintype "bidirectional"))
    )
    (net (code "73") (name "SPI2_LE") (class "Default")
      (node (ref "U$1") (pin "11") (pinfunction "2A0_11") (pintype "bidirectional"))
      (node (ref "U$1") (pin "8") (pinfunction "1A3_8") (pintype "bidirectional"))
      (node (ref "U0-C") (pin "29") (pinfunction "PA8_29") (pintype "bidirectional"))
    )
    (net (code "74") (name "SPI2_MISO") (class "Default")
      (node (ref "U$1") (pin "16") (pinfunction "1Y1_16") (pintype "bidirectional"))
      (node (ref "U$1") (pin "5") (pinfunction "2Y2_5") (pintype "bidirectional"))
      (node (ref "U0-C") (pin "27") (pinfunction "PB14_27") (pintype "bidirectional"))
    )
    (net (code "75") (name "SPI2_MOSI") (class "Default")
      (node (ref "U$1") (pin "13") (pinfunction "2A1_13") (pintype "bidirectional"))
      (node (ref "U$1") (pin "6") (pinfunction "1A2_6") (pintype "bidirectional"))
      (node (ref "U0-C") (pin "28") (pinfunction "PB15_28") (pintype "bidirectional"))
    )
    (net (code "76") (name "SPI2_REG") (class "Default")
      (node (ref "U$1") (pin "19") (pinfunction "2~{OE}_19") (pintype "bidirectional"))
      (node (ref "U$2") (pin "1") (pinfunction "1A_1") (pintype "bidirectional"))
      (node (ref "U0-C") (pin "25") (pinfunction "PB12_25") (pintype "bidirectional"))
    )
    (net (code "77") (name "SPI2_SCK") (class "Default")
      (node (ref "U$1") (pin "17") (pinfunction "2A3_17") (pintype "bidirectional"))
      (node (ref "U$1") (pin "2") (pinfunction "1A0_2") (pintype "bidirectional"))
      (node (ref "U$4") (pin "1") (pinfunction "1A_1") (pintype "bidirectional"))
      (node (ref "U$4") (pin "10") (pinfunction "3B_10") (pintype "bidirectional"))
      (node (ref "U$4") (pin "12") (pinfunction "4A_12") (pintype "bidirectional"))
      (node (ref "U$4") (pin "5") (pinfunction "2B_5") (pintype "bidirectional"))
      (node (ref "U0-C") (pin "26") (pinfunction "PB13_26") (pintype "bidirectional"))
    )
    (net (code "78") (name "SPI2_SCK0") (class "Default")
      (node (ref "U$18") (pin "3") (pinfunction "CLK_3") (pintype "bidirectional"))
      (node (ref "U$19") (pin "3") (pinfunction "CLK_3") (pintype "bidirectional"))
      (node (ref "U$20") (pin "3") (pinfunction "CLK_3") (pintype "bidirectional"))
      (node (ref "U$4") (pin "6") (pinfunction "2Y_6") (pintype "bidirectional"))
    )
    (net (code "79") (name "SPI2_SCK1") (class "Default")
      (node (ref "U$4") (pin "3") (pinfunction "1Y_3") (pintype "bidirectional"))
    )
    (net (code "80") (name "SPI2_SCK2") (class "Default")
      (node (ref "U$4") (pin "11") (pinfunction "4Y_11") (pintype "bidirectional"))
    )
    (net (code "81") (name "SPI2_SCK3") (class "Default")
      (node (ref "U$21") (pin "3") (pinfunction "CLK_3") (pintype "bidirectional"))
      (node (ref "U$4") (pin "8") (pinfunction "3Y_8") (pintype "bidirectional"))
    )
    (net (code "82") (name "ST") (class "Default")
      (node (ref "U$12") (pin "4") (pinfunction "ST_4") (pintype "bidirectional"))
      (node (ref "U$14") (pin "11") (pinfunction "4Y_11") (pintype "bidirectional"))
    )
    (net (code "83") (name "STATUS") (class "Default")
      (node (ref "U$12") (pin "6") (pinfunction "STATUS_6") (pintype "bidirectional"))
      (node (ref "U$14") (pin "5") (pinfunction "2B_5") (pintype "bidirectional"))
    )
    (net (code "84") (name "SWCLK") (class "Default")
      (node (ref "JP2") (pin "3") (pinfunction "3_3") (pintype "passive"))
      (node (ref "U0-C") (pin "37") (pinfunction "PA14_37") (pintype "bidirectional"))
    )
    (net (code "85") (name "SWDIO") (class "Default")
      (node (ref "JP2") (pin "4") (pinfunction "4_4") (pintype "passive"))
      (node (ref "U0-C") (pin "34") (pinfunction "PA13_34") (pintype "bidirectional"))
    )
    (net (code "86") (name "SWO") (class "Default")
      (node (ref "JP2") (pin "2") (pinfunction "2_2") (pintype "passive"))
      (node (ref "U0-C") (pin "39") (pinfunction "PB3_39") (pintype "bidirectional"))
    )
    (net (code "87") (name "U1-S_REGOUT") (class "Default")
      (node (ref "C5") (pin "1") (pinfunction "1_1") (pintype "passive"))
      (node (ref "U1-S") (pin "10") (pinfunction "REGOUT_10") (pintype "bidirectional"))
    )
    (net (code "88") (name "USART1_RX") (class "Default")
      (node (ref "U$15") (pin "TX") (pinfunction "TX_TX") (pintype "bidirectional"))
      (node (ref "U0-C") (pin "31") (pinfunction "PA10_31") (pintype "bidirectional"))
    )
    (net (code "89") (name "USART1_TX") (class "Default")
      (node (ref "U$15") (pin "RX") (pinfunction "RX_RX") (pintype "bidirectional"))
      (node (ref "U0-C") (pin "30") (pinfunction "PA9_30") (pintype "bidirectional"))
    )
    (net (code "90") (name "USART2_CTS") (class "Default")
      (node (ref "U0-C") (pin "10") (pinfunction "PA0_10") (pintype "bidirectional"))
    )
    (net (code "91") (name "USART2_RTS") (class "Default")
      (node (ref "U0-C") (pin "11") (pinfunction "PA1_11") (pintype "bidirectional"))
    )
    (net (code "92") (name "USART2_RX") (class "Default")
      (node (ref "U0-C") (pin "13") (pinfunction "PA3_13") (pintype "bidirectional"))
    )
    (net (code "93") (name "USART2_TX") (class "Default")
      (node (ref "U0-C") (pin "12") (pinfunction "PA2_12") (pintype "bidirectional"))
    )
    (net (code "94") (name "VBAT") (class "Default")
      (node (ref "U$15") (pin "VBACKUP") (pinfunction "VBACKUP_VBACKUP") (pintype "bidirectional"))
      (node (ref "U0-C") (pin "1") (pinfunction "VBAT_1") (pintype "bidirectional"))
    )
    (net (code "95") (name "VCAP_1") (class "Default")
      (node (ref "C1") (pin "1") (pinfunction "1_1") (pintype "passive"))
      (node (ref "U0-C") (pin "22") (pinfunction "VCAP_1_22") (pintype "bidirectional"))
    )
    (net (code "96") (name "VDDA") (class "Default")
      (node (ref "FB1") (pin "1") (pinfunction "1_1") (pintype "bidirectional"))
      (node (ref "U0-C") (pin "9") (pinfunction "VDDA/VREF-_9") (pintype "bidirectional"))
    )
    (net (code "97") (name "unconnected-(LED1-PadA)") (class "Default")
      (node (ref "LED1") (pin "A") (pinfunction "A_A") (pintype "passive"))
    )
    (net (code "98") (name "unconnected-(LED1-PadC)") (class "Default")
      (node (ref "LED1") (pin "C") (pinfunction "C_C") (pintype "passive"))
    )
    (net (code "99") (name "unconnected-(LED2-PadA)") (class "Default")
      (node (ref "LED2") (pin "A") (pinfunction "A_A") (pintype "passive"))
    )
    (net (code "100") (name "unconnected-(LED2-PadC)") (class "Default")
      (node (ref "LED2") (pin "C") (pinfunction "C_C") (pintype "passive"))
    )
    (net (code "101") (name "unconnected-(LED3-PadA)") (class "Default")
      (node (ref "LED3") (pin "A") (pinfunction "A_A") (pintype "passive"))
    )
    (net (code "102") (name "unconnected-(LED3-PadC)") (class "Default")
      (node (ref "LED3") (pin "C") (pinfunction "C_C") (pintype "passive"))
    )
    (net (code "103") (name "unconnected-(LED4-PadA)") (class "Default")
      (node (ref "LED4") (pin "A") (pinfunction "A_A") (pintype "passive"))
    )
    (net (code "104") (name "unconnected-(LED4-PadC)") (class "Default")
      (node (ref "LED4") (pin "C") (pinfunction "C_C") (pintype "passive"))
    )
    (net (code "105") (name "unconnected-(S1-S-Pad1)") (class "Default")
      (node (ref "S1") (pin "1") (pinfunction "S_1") (pintype "passive"))
    )
    (net (code "106") (name "unconnected-(S2-S1-Pad2)") (class "Default")
      (node (ref "S2") (pin "2") (pinfunction "S1_2") (pintype "passive"))
    )
    (net (code "107") (name "unconnected-(U$11-CSB-PadP$4)") (class "Default")
      (node (ref "U$11") (pin "P$4") (pinfunction "CSB_P$4") (pintype "bidirectional"))
    )
    (net (code "108") (name "unconnected-(U$14-1A-Pad1)") (class "Default")
      (node (ref "U$14") (pin "1") (pinfunction "1A_1") (pintype "bidirectional"))
    )
    (net (code "109") (name "unconnected-(U$14-1B-Pad2)") (class "Default")
      (node (ref "U$14") (pin "2") (pinfunction "1B_2") (pintype "bidirectional"))
    )
    (net (code "110") (name "unconnected-(U$14-1Y-Pad3)") (class "Default")
      (node (ref "U$14") (pin "3") (pinfunction "1Y_3") (pintype "bidirectional"))
    )
    (net (code "111") (name "unconnected-(U$14-2A-Pad4)") (class "Default")
      (node (ref "U$14") (pin "4") (pinfunction "2A_4") (pintype "bidirectional"))
    )
    (net (code "112") (name "unconnected-(U$15-NREST-PadNRESET)") (class "Default")
      (node (ref "U$15") (pin "NRESET") (pinfunction "NREST_NRESET") (pintype "bidirectional"))
    )
    (net (code "113") (name "unconnected-(U$15-Pad1PPS)") (class "Default")
      (node (ref "U$15") (pin "1PPS") (pinfunction "1PPS_1PPS") (pintype "bidirectional"))
    )
    (net (code "114") (name "unconnected-(U$15-Pad3D-FIX)") (class "Default")
      (node (ref "U$15") (pin "3D-FIX") (pinfunction "3D-FIX_3D-FIX") (pintype "bidirectional"))
    )
    (net (code "115") (name "unconnected-(U$15-PadRTCM)") (class "Default")
      (node (ref "U$15") (pin "RTCM") (pinfunction "RTCM_RTCM") (pintype "bidirectional"))
    )
    (net (code "116") (name "unconnected-(U$18-SDO-Pad14)") (class "Default")
      (node (ref "U$18") (pin "14") (pinfunction "SDO_14") (pintype "bidirectional"))
    )
    (net (code "117") (name "unconnected-(U$18-~{OUT0}-Pad5)") (class "Default")
      (node (ref "U$18") (pin "5") (pinfunction "~{OUT0}_5") (pintype "bidirectional"))
    )
    (net (code "118") (name "unconnected-(U$18-~{OUT1}-Pad6)") (class "Default")
      (node (ref "U$18") (pin "6") (pinfunction "~{OUT1}_6") (pintype "bidirectional"))
    )
    (net (code "119") (name "unconnected-(U$18-~{OUT2}-Pad7)") (class "Default")
      (node (ref "U$18") (pin "7") (pinfunction "~{OUT2}_7") (pintype "bidirectional"))
    )
    (net (code "120") (name "unconnected-(U$18-~{OUT3}-Pad8)") (class "Default")
      (node (ref "U$18") (pin "8") (pinfunction "~{OUT3}_8") (pintype "bidirectional"))
    )
    (net (code "121") (name "unconnected-(U$18-~{OUT4}-Pad9)") (class "Default")
      (node (ref "U$18") (pin "9") (pinfunction "~{OUT4}_9") (pintype "bidirectional"))
    )
    (net (code "122") (name "unconnected-(U$18-~{OUT5}-Pad10)") (class "Default")
      (node (ref "U$18") (pin "10") (pinfunction "~{OUT5}_10") (pintype "bidirectional"))
    )
    (net (code "123") (name "unconnected-(U$18-~{OUT6}-Pad11)") (class "Default")
      (node (ref "U$18") (pin "11") (pinfunction "~{OUT6}_11") (pintype "bidirectional"))
    )
    (net (code "124") (name "unconnected-(U$18-~{OUT7}-Pad12)") (class "Default")
      (node (ref "U$18") (pin "12") (pinfunction "~{OUT7}_12") (pintype "bidirectional"))
    )
    (net (code "125") (name "unconnected-(U$19-SDO-Pad14)") (class "Default")
      (node (ref "U$19") (pin "14") (pinfunction "SDO_14") (pintype "bidirectional"))
    )
    (net (code "126") (name "unconnected-(U$19-~{OUT0}-Pad5)") (class "Default")
      (node (ref "U$19") (pin "5") (pinfunction "~{OUT0}_5") (pintype "bidirectional"))
    )
    (net (code "127") (name "unconnected-(U$19-~{OUT1}-Pad6)") (class "Default")
      (node (ref "U$19") (pin "6") (pinfunction "~{OUT1}_6") (pintype "bidirectional"))
    )
    (net (code "128") (name "unconnected-(U$19-~{OUT2}-Pad7)") (class "Default")
      (node (ref "U$19") (pin "7") (pinfunction "~{OUT2}_7") (pintype "bidirectional"))
    )
    (net (code "129") (name "unconnected-(U$19-~{OUT3}-Pad8)") (class "Default")
      (node (ref "U$19") (pin "8") (pinfunction "~{OUT3}_8") (pintype "bidirectional"))
    )
    (net (code "130") (name "unconnected-(U$19-~{OUT4}-Pad9)") (class "Default")
      (node (ref "U$19") (pin "9") (pinfunction "~{OUT4}_9") (pintype "bidirectional"))
    )
    (net (code "131") (name "unconnected-(U$19-~{OUT5}-Pad10)") (class "Default")
      (node (ref "U$19") (pin "10") (pinfunction "~{OUT5}_10") (pintype "bidirectional"))
    )
    (net (code "132") (name "unconnected-(U$19-~{OUT6}-Pad11)") (class "Default")
      (node (ref "U$19") (pin "11") (pinfunction "~{OUT6}_11") (pintype "bidirectional"))
    )
    (net (code "133") (name "unconnected-(U$19-~{OUT7}-Pad12)") (class "Default")
      (node (ref "U$19") (pin "12") (pinfunction "~{OUT7}_12") (pintype "bidirectional"))
    )
    (net (code "134") (name "unconnected-(U$20-OUT0-Pad5)") (class "Default")
      (node (ref "U$20") (pin "5") (pinfunction "OUT0_5") (pintype "bidirectional"))
    )
    (net (code "135") (name "unconnected-(U$20-OUT1-Pad6)") (class "Default")
      (node (ref "U$20") (pin "6") (pinfunction "OUT1_6") (pintype "bidirectional"))
    )
    (net (code "136") (name "unconnected-(U$20-OUT2-Pad7)") (class "Default")
      (node (ref "U$20") (pin "7") (pinfunction "OUT2_7") (pintype "bidirectional"))
    )
    (net (code "137") (name "unconnected-(U$20-OUT3-Pad8)") (class "Default")
      (node (ref "U$20") (pin "8") (pinfunction "OUT3_8") (pintype "bidirectional"))
    )
    (net (code "138") (name "unconnected-(U$20-OUT4-Pad9)") (class "Default")
      (node (ref "U$20") (pin "9") (pinfunction "OUT4_9") (pintype "bidirectional"))
    )
    (net (code "139") (name "unconnected-(U$20-OUT5-Pad10)") (class "Default")
      (node (ref "U$20") (pin "10") (pinfunction "OUT5_10") (pintype "bidirectional"))
    )
    (net (code "140") (name "unconnected-(U$20-OUT6-Pad11)") (class "Default")
      (node (ref "U$20") (pin "11") (pinfunction "OUT6_11") (pintype "bidirectional"))
    )
    (net (code "141") (name "unconnected-(U$20-OUT7-Pad12)") (class "Default")
      (node (ref "U$20") (pin "12") (pinfunction "OUT7_12") (pintype "bidirectional"))
    )
    (net (code "142") (name "unconnected-(U$20-OUT8-Pad13)") (class "Default")
      (node (ref "U$20") (pin "13") (pinfunction "OUT8_13") (pintype "bidirectional"))
    )
    (net (code "143") (name "unconnected-(U$20-OUT9-Pad14)") (class "Default")
      (node (ref "U$20") (pin "14") (pinfunction "OUT9_14") (pintype "bidirectional"))
    )
    (net (code "144") (name "unconnected-(U$20-OUT10-Pad15)") (class "Default")
      (node (ref "U$20") (pin "15") (pinfunction "OUT10_15") (pintype "bidirectional"))
    )
    (net (code "145") (name "unconnected-(U$20-OUT11-Pad16)") (class "Default")
      (node (ref "U$20") (pin "16") (pinfunction "OUT11_16") (pintype "bidirectional"))
    )
    (net (code "146") (name "unconnected-(U$20-OUT12-Pad17)") (class "Default")
      (node (ref "U$20") (pin "17") (pinfunction "OUT12_17") (pintype "bidirectional"))
    )
    (net (code "147") (name "unconnected-(U$20-OUT13-Pad18)") (class "Default")
      (node (ref "U$20") (pin "18") (pinfunction "OUT13_18") (pintype "bidirectional"))
    )
    (net (code "148") (name "unconnected-(U$20-OUT14-Pad19)") (class "Default")
      (node (ref "U$20") (pin "19") (pinfunction "OUT14_19") (pintype "bidirectional"))
    )
    (net (code "149") (name "unconnected-(U$20-OUT15-Pad20)") (class "Default")
      (node (ref "U$20") (pin "20") (pinfunction "OUT15_20") (pintype "bidirectional"))
    )
    (net (code "150") (name "unconnected-(U$20-SDO-Pad22)") (class "Default")
      (node (ref "U$20") (pin "22") (pinfunction "SDO_22") (pintype "bidirectional"))
    )
    (net (code "151") (name "unconnected-(U$21-OUT0-Pad5)") (class "Default")
      (node (ref "U$21") (pin "5") (pinfunction "OUT0_5") (pintype "bidirectional"))
    )
    (net (code "152") (name "unconnected-(U$21-OUT1-Pad6)") (class "Default")
      (node (ref "U$21") (pin "6") (pinfunction "OUT1_6") (pintype "bidirectional"))
    )
    (net (code "153") (name "unconnected-(U$21-OUT2-Pad7)") (class "Default")
      (node (ref "U$21") (pin "7") (pinfunction "OUT2_7") (pintype "bidirectional"))
    )
    (net (code "154") (name "unconnected-(U$21-OUT3-Pad8)") (class "Default")
      (node (ref "U$21") (pin "8") (pinfunction "OUT3_8") (pintype "bidirectional"))
    )
    (net (code "155") (name "unconnected-(U$21-OUT4-Pad9)") (class "Default")
      (node (ref "U$21") (pin "9") (pinfunction "OUT4_9") (pintype "bidirectional"))
    )
    (net (code "156") (name "unconnected-(U$21-OUT5-Pad10)") (class "Default")
      (node (ref "U$21") (pin "10") (pinfunction "OUT5_10") (pintype "bidirectional"))
    )
    (net (code "157") (name "unconnected-(U$21-OUT6-Pad11)") (class "Default")
      (node (ref "U$21") (pin "11") (pinfunction "OUT6_11") (pintype "bidirectional"))
    )
    (net (code "158") (name "unconnected-(U$21-OUT7-Pad12)") (class "Default")
      (node (ref "U$21") (pin "12") (pinfunction "OUT7_12") (pintype "bidirectional"))
    )
    (net (code "159") (name "unconnected-(U$21-OUT8-Pad13)") (class "Default")
      (node (ref "U$21") (pin "13") (pinfunction "OUT8_13") (pintype "bidirectional"))
    )
    (net (code "160") (name "unconnected-(U$21-OUT9-Pad14)") (class "Default")
      (node (ref "U$21") (pin "14") (pinfunction "OUT9_14") (pintype "bidirectional"))
    )
    (net (code "161") (name "unconnected-(U$21-OUT10-Pad15)") (class "Default")
      (node (ref "U$21") (pin "15") (pinfunction "OUT10_15") (pintype "bidirectional"))
    )
    (net (code "162") (name "unconnected-(U$21-OUT11-Pad16)") (class "Default")
      (node (ref "U$21") (pin "16") (pinfunction "OUT11_16") (pintype "bidirectional"))
    )
    (net (code "163") (name "unconnected-(U$21-OUT12-Pad17)") (class "Default")
      (node (ref "U$21") (pin "17") (pinfunction "OUT12_17") (pintype "bidirectional"))
    )
    (net (code "164") (name "unconnected-(U$21-OUT13-Pad18)") (class "Default")
      (node (ref "U$21") (pin "18") (pinfunction "OUT13_18") (pintype "bidirectional"))
    )
    (net (code "165") (name "unconnected-(U$21-OUT14-Pad19)") (class "Default")
      (node (ref "U$21") (pin "19") (pinfunction "OUT14_19") (pintype "bidirectional"))
    )
    (net (code "166") (name "unconnected-(U$21-OUT15-Pad20)") (class "Default")
      (node (ref "U$21") (pin "20") (pinfunction "OUT15_20") (pintype "bidirectional"))
    )
    (net (code "167") (name "unconnected-(U$21-SDO-Pad22)") (class "Default")
      (node (ref "U$21") (pin "22") (pinfunction "SDO_22") (pintype "bidirectional"))
    )
    (net (code "168") (name "unconnected-(U1-S-AUX_CL-Pad7)") (class "Default")
      (node (ref "U1-S") (pin "7") (pinfunction "AUX_CL_7") (pintype "bidirectional"))
    )
    (net (code "169") (name "unconnected-(U1-S-AUX_DA-Pad21)") (class "Default")
      (node (ref "U1-S") (pin "21") (pinfunction "AUX_DA_21") (pintype "bidirectional"))
    )
    (net (code "170") (name "unconnected-(U1-S-FSYNC-Pad11)") (class "Default")
      (node (ref "U1-S") (pin "11") (pinfunction "FSYNC_11") (pintype "bidirectional"))
    )
    (net (code "171") (name "unconnected-(U1-S-INT1-Pad12)") (class "Default")
      (node (ref "U1-S") (pin "12") (pinfunction "INT1_12") (pintype "bidirectional"))
    )
    (net (code "172") (name "unconnected-(U1-S-NC.1-Pad1)") (class "Default")
      (node (ref "U1-S") (pin "1") (pinfunction "NC.1_1") (pintype "bidirectional"))
    )
    (net (code "173") (name "unconnected-(U1-S-NC.2-Pad2)") (class "Default")
      (node (ref "U1-S") (pin "2") (pinfunction "NC.2_2") (pintype "bidirectional"))
    )
    (net (code "174") (name "unconnected-(U1-S-NC.3-Pad3)") (class "Default")
      (node (ref "U1-S") (pin "3") (pinfunction "NC.3_3") (pintype "bidirectional"))
    )
    (net (code "175") (name "unconnected-(U1-S-NC.4-Pad4)") (class "Default")
      (node (ref "U1-S") (pin "4") (pinfunction "NC.4_4") (pintype "bidirectional"))
    )
    (net (code "176") (name "unconnected-(U1-S-NC.5-Pad5)") (class "Default")
      (node (ref "U1-S") (pin "5") (pinfunction "NC.5_5") (pintype "bidirectional"))
    )
    (net (code "177") (name "unconnected-(U1-S-NC.6-Pad6)") (class "Default")
      (node (ref "U1-S") (pin "6") (pinfunction "NC.6_6") (pintype "bidirectional"))
    )
    (net (code "178") (name "unconnected-(U1-S-NC.14-Pad14)") (class "Default")
      (node (ref "U1-S") (pin "14") (pinfunction "NC.14_14") (pintype "bidirectional"))
    )
    (net (code "179") (name "unconnected-(U1-S-NC.15-Pad15)") (class "Default")
      (node (ref "U1-S") (pin "15") (pinfunction "NC.15_15") (pintype "bidirectional"))
    )
    (net (code "180") (name "unconnected-(U1-S-NC.16-Pad16)") (class "Default")
      (node (ref "U1-S") (pin "16") (pinfunction "NC.16_16") (pintype "bidirectional"))
    )
    (net (code "181") (name "unconnected-(U1-S-NC.17-Pad17)") (class "Default")
      (node (ref "U1-S") (pin "17") (pinfunction "NC.17_17") (pintype "bidirectional"))
    )
    (net (code "182") (name "unconnected-(U1-S-RESV.NC-Pad19)") (class "Default")
      (node (ref "U1-S") (pin "19") (pinfunction "RESV.NC_19") (pintype "bidirectional"))
    )
    (net (code "183") (name "~{SPI1_REG}") (class "Default")
      (node (ref "U$2") (pin "4") (pinfunction "2Y_4") (pintype "bidirectional"))
      (node (ref "U$3") (pin "19") (pinfunction "2~{OE}_19") (pintype "bidirectional"))
    )
    (net (code "184") (name "~{SPI2_REG}") (class "Default")
      (node (ref "U$1") (pin "1") (pinfunction "1~{OE}_1") (pintype "bidirectional"))
      (node (ref "U$2") (pin "6") (pinfunction "1Y_6") (pintype "bidirectional"))
    )
  )
)
